# D1ZIG.net
KiCad netlist of a schematic drawn in EAGLE
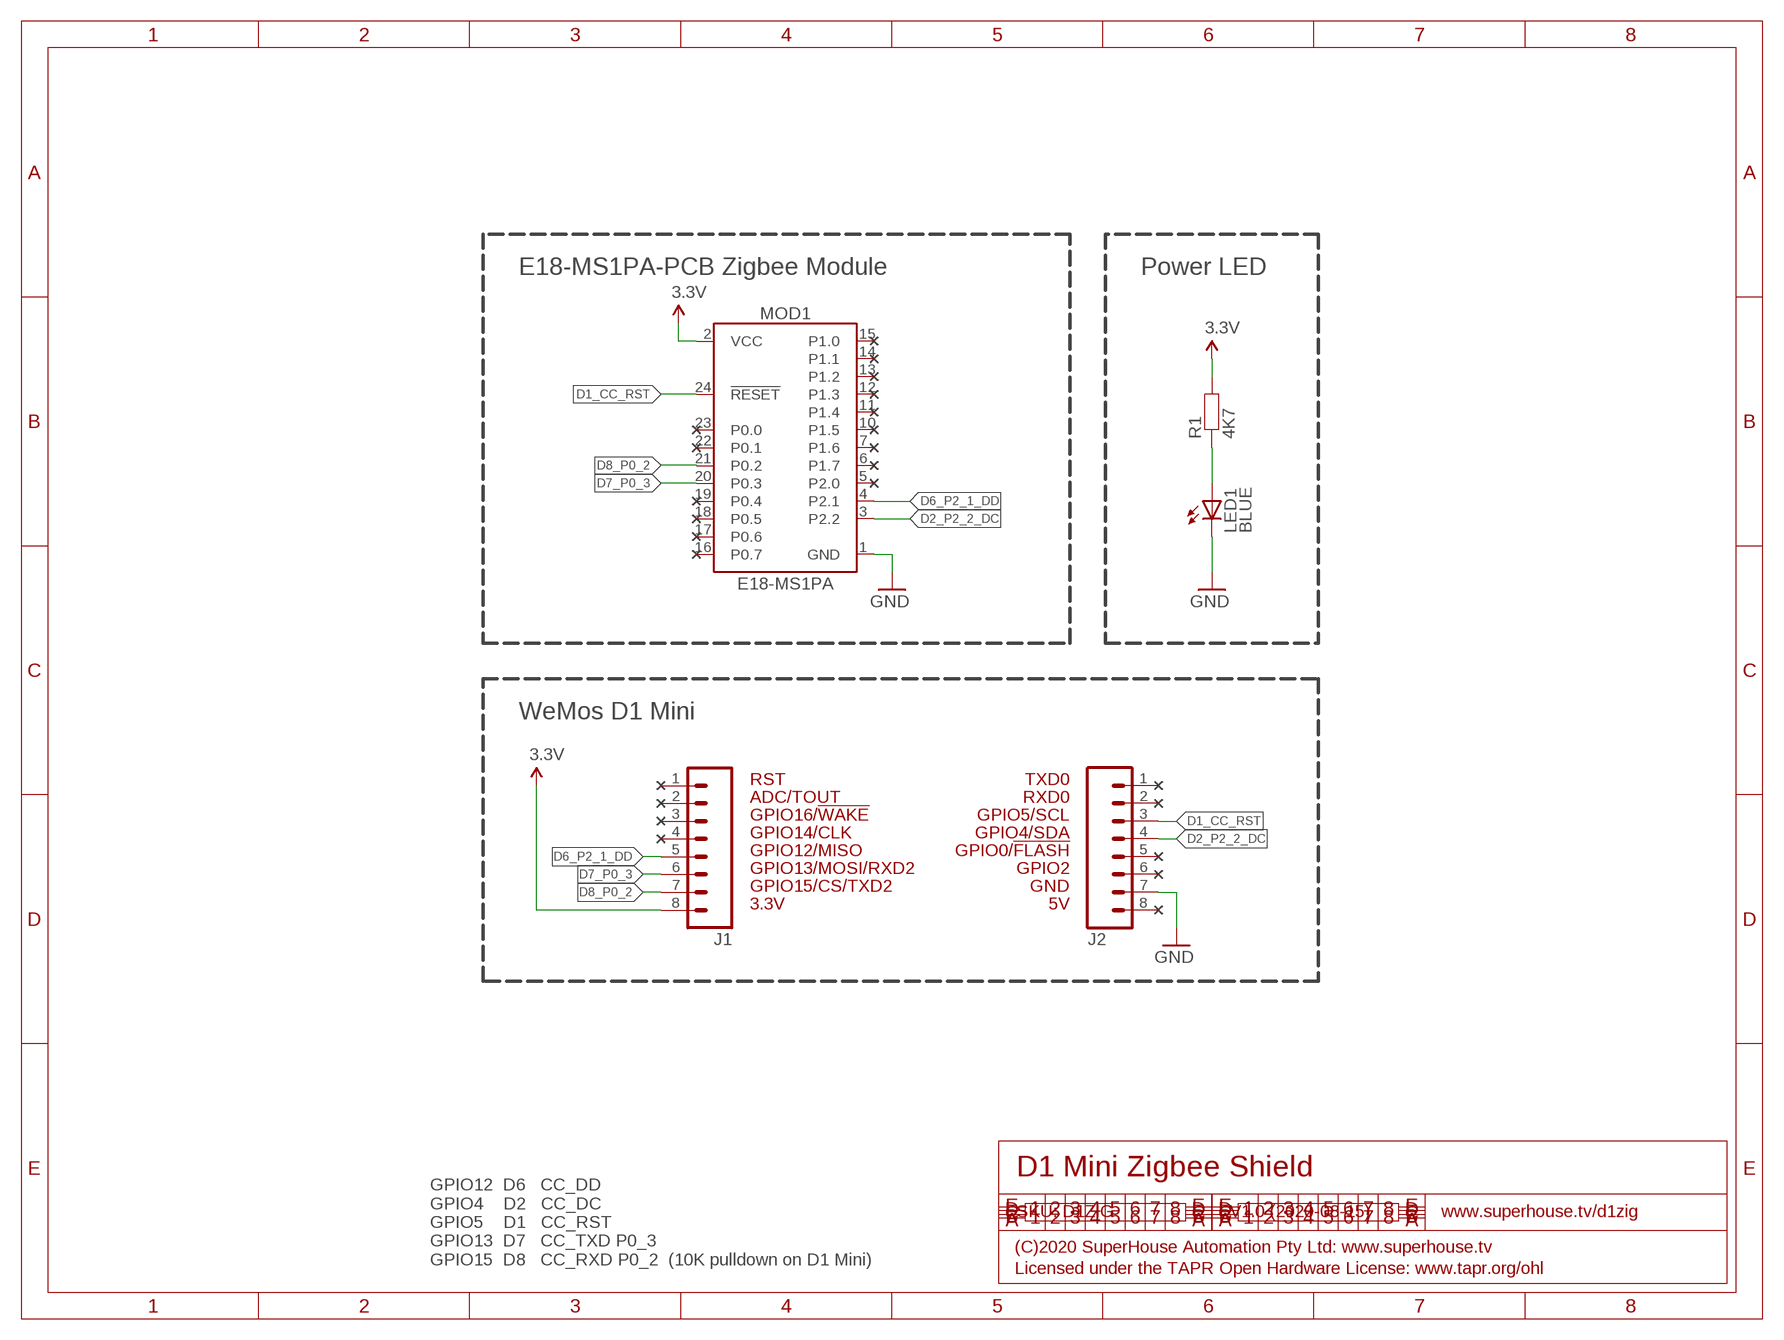
[diagram p0: schematic, sheet 1]

(export (version "E")
  (design (tool "Eeschema 10.0.6"))
  (components
    (comp (ref "J1")
      (value "M08")
      (footprint "eagle-import:1X08")
      (libsource (lib "eagle-import") (part "M08"))
    )
    (comp (ref "J2")
      (value "M08")
      (footprint "eagle-import:1X08")
      (libsource (lib "eagle-import") (part "M08"))
    )
    (comp (ref "LED1")
      (value "BLUE")
      (footprint "eagle-import:LED-0603")
      (libsource (lib "eagle-import") (part "LED0603"))
    )
    (comp (ref "MOD1")
      (value "E18-MS1PA")
      (footprint "eagle-import:E18-MS1PA-PCB")
      (libsource (lib "eagle-import") (part "E18-MS1PA"))
    )
    (comp (ref "R1")
      (value "4K7")
      (footprint "eagle-import:R0603")
      (libsource (lib "eagle-import") (part "RESISTOR0603"))
    )
  )
  (nets
    (net (code "1") (name "3.3V") (class "Default")
      (node (ref "J1") (pin "8") (pinfunction "8_8") (pintype "passive"))
      (node (ref "MOD1") (pin "2") (pinfunction "VCC_2") (pintype "power_in"))
      (node (ref "R1") (pin "2") (pinfunction "2_2") (pintype "passive"))
    )
    (net (code "2") (name "D1_CC_RST") (class "Default")
      (node (ref "J2") (pin "3") (pinfunction "3_3") (pintype "passive"))
      (node (ref "MOD1") (pin "24") (pinfunction "~{RESET}_24") (pintype "bidirectional"))
    )
    (net (code "3") (name "D2_P2_2_DC") (class "Default")
      (node (ref "J2") (pin "4") (pinfunction "4_4") (pintype "passive"))
      (node (ref "MOD1") (pin "3") (pinfunction "P2.2_3") (pintype "bidirectional"))
    )
    (net (code "4") (name "D6_P2_1_DD") (class "Default")
      (node (ref "J1") (pin "5") (pinfunction "5_5") (pintype "passive"))
      (node (ref "MOD1") (pin "4") (pinfunction "P2.1_4") (pintype "bidirectional"))
    )
    (net (code "5") (name "D7_P0_3") (class "Default")
      (node (ref "J1") (pin "6") (pinfunction "6_6") (pintype "passive"))
      (node (ref "MOD1") (pin "20") (pinfunction "P0.3_20") (pintype "bidirectional"))
    )
    (net (code "6") (name "D8_P0_2") (class "Default")
      (node (ref "J1") (pin "7") (pinfunction "7_7") (pintype "passive"))
      (node (ref "MOD1") (pin "21") (pinfunction "P0.2_21") (pintype "bidirectional"))
    )
    (net (code "7") (name "GND") (class "Default")
      (node (ref "J2") (pin "7") (pinfunction "7_7") (pintype "passive"))
      (node (ref "LED1") (pin "C") (pinfunction "C_C") (pintype "passive"))
      (node (ref "MOD1") (pin "1") (pinfunction "GND_1") (pintype "bidirectional"))
    )
    (net (code "8") (name "Net-(LED1-PadA)") (class "Default")
      (node (ref "LED1") (pin "A") (pinfunction "A_A") (pintype "passive"))
      (node (ref "R1") (pin "1") (pinfunction "1_1") (pintype "passive"))
    )
    (net (code "9") (name "unconnected-(J1-Pad1)") (class "Default")
      (node (ref "J1") (pin "1") (pinfunction "1_1") (pintype "passive"))
    )
    (net (code "10") (name "unconnected-(J1-Pad2)") (class "Default")
      (node (ref "J1") (pin "2") (pinfunction "2_2") (pintype "passive"))
    )
    (net (code "11") (name "unconnected-(J1-Pad3)") (class "Default")
      (node (ref "J1") (pin "3") (pinfunction "3_3") (pintype "passive"))
    )
    (net (code "12") (name "unconnected-(J1-Pad4)") (class "Default")
      (node (ref "J1") (pin "4") (pinfunction "4_4") (pintype "passive"))
    )
    (net (code "13") (name "unconnected-(J2-Pad1)") (class "Default")
      (node (ref "J2") (pin "1") (pinfunction "1_1") (pintype "passive"))
    )
    (net (code "14") (name "unconnected-(J2-Pad2)") (class "Default")
      (node (ref "J2") (pin "2") (pinfunction "2_2") (pintype "passive"))
    )
    (net (code "15") (name "unconnected-(J2-Pad5)") (class "Default")
      (node (ref "J2") (pin "5") (pinfunction "5_5") (pintype "passive"))
    )
    (net (code "16") (name "unconnected-(J2-Pad6)") (class "Default")
      (node (ref "J2") (pin "6") (pinfunction "6_6") (pintype "passive"))
    )
    (net (code "17") (name "unconnected-(J2-Pad8)") (class "Default")
      (node (ref "J2") (pin "8") (pinfunction "8_8") (pintype "passive"))
    )
    (net (code "18") (name "unconnected-(MOD1-P0.0-Pad23)") (class "Default")
      (node (ref "MOD1") (pin "23") (pinfunction "P0.0_23") (pintype "bidirectional"))
    )
    (net (code "19") (name "unconnected-(MOD1-P0.1-Pad22)") (class "Default")
      (node (ref "MOD1") (pin "22") (pinfunction "P0.1_22") (pintype "bidirectional"))
    )
    (net (code "20") (name "unconnected-(MOD1-P0.4-Pad19)") (class "Default")
      (node (ref "MOD1") (pin "19") (pinfunction "P0.4_19") (pintype "bidirectional"))
    )
    (net (code "21") (name "unconnected-(MOD1-P0.5-Pad18)") (class "Default")
      (node (ref "MOD1") (pin "18") (pinfunction "P0.5_18") (pintype "bidirectional"))
    )
    (net (code "22") (name "unconnected-(MOD1-P0.6-Pad17)") (class "Default")
      (node (ref "MOD1") (pin "17") (pinfunction "P0.6_17") (pintype "bidirectional"))
    )
    (net (code "23") (name "unconnected-(MOD1-P0.7-Pad16)") (class "Default")
      (node (ref "MOD1") (pin "16") (pinfunction "P0.7_16") (pintype "bidirectional"))
    )
    (net (code "24") (name "unconnected-(MOD1-P1.0-Pad15)") (class "Default")
      (node (ref "MOD1") (pin "15") (pinfunction "P1.0_15") (pintype "bidirectional"))
    )
    (net (code "25") (name "unconnected-(MOD1-P1.1-Pad14)") (class "Default")
      (node (ref "MOD1") (pin "14") (pinfunction "P1.1_14") (pintype "bidirectional"))
    )
    (net (code "26") (name "unconnected-(MOD1-P1.2-Pad13)") (class "Default")
      (node (ref "MOD1") (pin "13") (pinfunction "P1.2_13") (pintype "bidirectional"))
    )
    (net (code "27") (name "unconnected-(MOD1-P1.3-Pad12)") (class "Default")
      (node (ref "MOD1") (pin "12") (pinfunction "P1.3_12") (pintype "bidirectional"))
    )
    (net (code "28") (name "unconnected-(MOD1-P1.4-Pad11)") (class "Default")
      (node (ref "MOD1") (pin "11") (pinfunction "P1.4_11") (pintype "bidirectional"))
    )
    (net (code "29") (name "unconnected-(MOD1-P1.5-Pad10)") (class "Default")
      (node (ref "MOD1") (pin "10") (pinfunction "P1.5_10") (pintype "bidirectional"))
    )
    (net (code "30") (name "unconnected-(MOD1-P1.6-Pad7)") (class "Default")
      (node (ref "MOD1") (pin "7") (pinfunction "P1.6_7") (pintype "bidirectional"))
    )
    (net (code "31") (name "unconnected-(MOD1-P1.7-Pad6)") (class "Default")
      (node (ref "MOD1") (pin "6") (pinfunction "P1.7_6") (pintype "bidirectional"))
    )
    (net (code "32") (name "unconnected-(MOD1-P2.0-Pad5)") (class "Default")
      (node (ref "MOD1") (pin "5") (pinfunction "P2.0_5") (pintype "bidirectional"))
    )
  )
)
